# MB1-Pwr-r1_0.net
KiCad netlist of a schematic drawn in Altium Designer
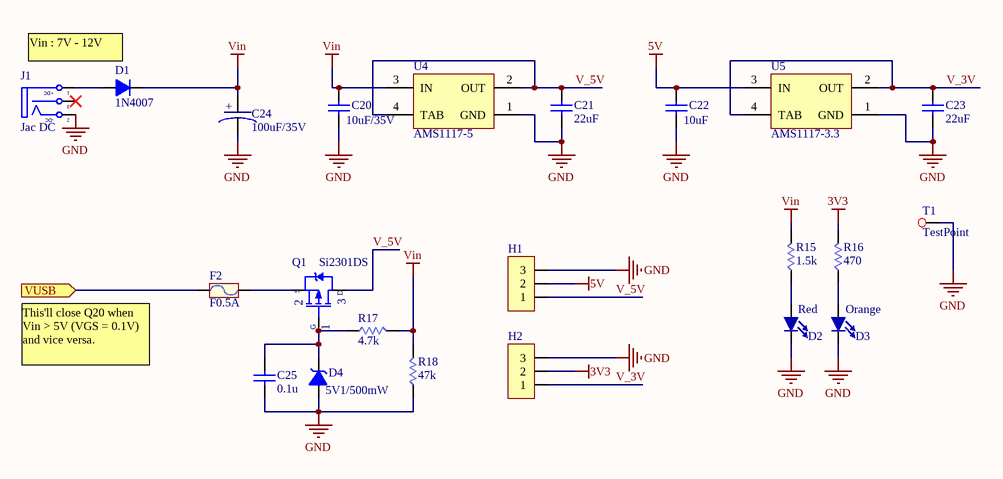
[diagram p0: MB1-Pwr-r1.0.SchDoc]

(export (version "E")
  (design (tool "Eeschema 10.0.6"))
  (components
    (comp (ref "C20")
      (value "10uF/35V")
      (footprint "SM-1210")
      (description "Non-polarity ceramic capacitor")
      (fields (field (name "Comment") "CAP Ceramic") (field (name "PUBLISHER") "Altium Limited"))
      (libsource (lib "HLib_schematic_lib") (part "CAP Ceramic"))
    )
    (comp (ref "C21")
      (value "22uF")
      (footprint "SM_0805_C_CERAMIC")
      (description "Non-polarity ceramic capacitor")
      (fields (field (name "Comment") "CAP Ceramic") (field (name "PUBLISHER") "Altium Limited"))
      (libsource (lib "HLib_schematic_lib") (part "CAP Ceramic"))
    )
    (comp (ref "C22")
      (value "10uF")
      (footprint "SM_0805_C_CERAMIC")
      (description "Non-polarity ceramic capacitor")
      (fields (field (name "Comment") "CAP Ceramic") (field (name "PUBLISHER") "Altium Limited"))
      (libsource (lib "HLib_schematic_lib") (part "CAP Ceramic"))
    )
    (comp (ref "C23")
      (value "22uF")
      (footprint "SM_0805_C_CERAMIC")
      (description "Non-polarity ceramic capacitor")
      (fields (field (name "Comment") "CAP Ceramic") (field (name "PUBLISHER") "Altium Limited"))
      (libsource (lib "HLib_schematic_lib") (part "CAP Ceramic"))
    )
    (comp (ref "C24")
      (value "100uF/35V")
      (footprint "Cap-Alu-D8")
      (fields (field (name "Comment") "CapT"))
      (libsource (lib "MyLib") (part "CapA"))
    )
    (comp (ref "C25")
      (value "0.1u")
      (footprint "SM_0805_C_CERAMIC")
      (description "Non-polarity ceramic capacitor")
      (fields (field (name "Comment") "CAP Ceramic") (field (name "PUBLISHER") "Altium Limited"))
      (libsource (lib "HLib_schematic_lib") (part "CAP Ceramic"))
    )
    (comp (ref "D1")
      (value "1N4007")
      (footprint "DO-214AC")
      (description "Diode 1A")
      (libsource (lib "VioletofSun") (part "D1A"))
    )
    (comp (ref "D2")
      (value "Red")
      (footprint "SM_0805_POL_LD")
      (description "LED")
      (fields (field (name "PUBLISHER") "Altium Limited"))
      (libsource (lib "HLib_schematic_lib") (part "LED"))
    )
    (comp (ref "D3")
      (value "Orange")
      (footprint "SM_0805_POL_LD")
      (description "LED")
      (fields (field (name "PUBLISHER") "Altium Limited"))
      (libsource (lib "HLib_schematic_lib") (part "LED"))
    )
    (comp (ref "D4")
      (value "5V1/500mW")
      (footprint "SOD-123")
      (description "Diode Zenner")
      (libsource (lib "VioletofSun") (part "DZ"))
    )
    (comp (ref "F2")
      (value "F0.5A")
      (footprint "SMD-1812")
      (description "Fuse")
      (fields (field (name "DESIGNED BY") "VanDungEvn"))
      (libsource (lib "VioletofSun") (part "Fuse"))
    )
    (comp (ref "H1") (value "Hed3") (footprint "Hed3") (libsource (lib "MyLib") (part "Hed3")))
    (comp (ref "H2") (value "Hed3") (footprint "Hed3") (libsource (lib "MyLib") (part "Hed3")))
    (comp (ref "J1")
      (value "Jac DC")
      (footprint "DCJack")
      (description "Jac DC input")
      (libsource (lib "VioletofSun") (part "DCIN"))
    )
    (comp (ref "Q1")
      (value "Si2301DS")
      (footprint "SOT23")
      (description "P-Channel 1.25-W, 2.5-V MOSFET")
      (libsource (lib "MyLib") (part "P-MOSFET"))
    )
    (comp (ref "R15")
      (value "1.5k")
      (footprint "SM_0805_R")
      (description "Resistor")
      (fields (field (name "PUBLISHER") "Altium Limited"))
      (libsource (lib "HLib_schematic_lib") (part "R"))
    )
    (comp (ref "R16")
      (value "470")
      (footprint "SM_0805_R")
      (description "Resistor")
      (fields (field (name "PUBLISHER") "Altium Limited"))
      (libsource (lib "HLib_schematic_lib") (part "R"))
    )
    (comp (ref "R17")
      (value "4.7k")
      (footprint "SM_0805_R")
      (description "Resistor")
      (fields (field (name "PUBLISHER") "Altium Limited"))
      (libsource (lib "HLib_schematic_lib") (part "R"))
    )
    (comp (ref "R18")
      (value "47k")
      (footprint "SM_0805_R")
      (description "Resistor")
      (fields (field (name "PUBLISHER") "Altium Limited"))
      (libsource (lib "HLib_schematic_lib") (part "R"))
    )
    (comp (ref "T1") (value "TestPoint") (footprint "TestPoint") (libsource (lib "MyLib") (part "TestPoint")))
    (comp (ref "U4")
      (value "AMS1117-5")
      (footprint "MP04A_N")
      (description "800mA Low-Dropout Linear Regulator, 4-pin SOT-223")
      (fields
        (field (name "PARTNUMBER") "LM1117IMP-3.3")
        (field (name "MANUFACTURER") "National Semiconductor")
        (field (name "PUBLISHER") "Altium Limited")
      )
      (libsource (lib "NSC LDO") (part "LM1117IMP-3.3"))
    )
    (comp (ref "U5")
      (value "AMS1117-3.3")
      (footprint "MP04A_N")
      (description "800mA Low-Dropout Linear Regulator, 4-pin SOT-223")
      (fields
        (field (name "PARTNUMBER") "LM1117IMP-3.3")
        (field (name "MANUFACTURER") "National Semiconductor")
        (field (name "PUBLISHER") "Altium Limited")
      )
      (libsource (lib "NSC LDO") (part "LM1117IMP-3.3"))
    )
  )
  (nets
    (net (code "1") (name "/VUSB") (class "Default")
      (node (ref "F2") (pin "1") (pinfunction "1_1") (pintype "passive"))
    )
    (net (code "2") (name "/V_3V") (class "Default")
      (node (ref "C23") (pin "2") (pinfunction "2_2") (pintype "passive"))
      (node (ref "H2") (pin "1") (pinfunction "1_1") (pintype "passive"))
      (node (ref "U5") (pin "2") (pinfunction "OUT_2") (pintype "power_in"))
      (node (ref "U5") (pin "4") (pinfunction "TAB_4") (pintype "power_in"))
    )
    (net (code "3") (name "/V_5V") (class "Default")
      (node (ref "C21") (pin "2") (pinfunction "2_2") (pintype "passive"))
      (node (ref "H1") (pin "1") (pinfunction "1_1") (pintype "passive"))
      (node (ref "Q1") (pin "3") (pinfunction "D_3") (pintype "passive"))
      (node (ref "U4") (pin "2") (pinfunction "OUT_2") (pintype "power_in"))
      (node (ref "U4") (pin "4") (pinfunction "TAB_4") (pintype "power_in"))
    )
    (net (code "4") (name "3V3") (class "Default")
      (node (ref "H2") (pin "2") (pinfunction "2_2") (pintype "passive"))
      (node (ref "R16") (pin "2") (pinfunction "2_2") (pintype "passive"))
    )
    (net (code "5") (name "5V") (class "Default")
      (node (ref "C22") (pin "2") (pinfunction "2_2") (pintype "passive"))
      (node (ref "H1") (pin "2") (pinfunction "2_2") (pintype "passive"))
      (node (ref "U5") (pin "3") (pinfunction "IN_3") (pintype "power_in"))
    )
    (net (code "6") (name "GND") (class "Default")
      (node (ref "C20") (pin "1") (pinfunction "1_1") (pintype "passive"))
      (node (ref "C21") (pin "1") (pinfunction "1_1") (pintype "passive"))
      (node (ref "C22") (pin "1") (pinfunction "1_1") (pintype "passive"))
      (node (ref "C23") (pin "1") (pinfunction "1_1") (pintype "passive"))
      (node (ref "C24") (pin "2") (pinfunction "-_2") (pintype "passive"))
      (node (ref "C25") (pin "1") (pinfunction "1_1") (pintype "passive"))
      (node (ref "D2") (pin "2") (pinfunction "K_2") (pintype "passive"))
      (node (ref "D3") (pin "2") (pinfunction "K_2") (pintype "passive"))
      (node (ref "D4") (pin "1") (pinfunction "A_1") (pintype "passive"))
      (node (ref "H1") (pin "3") (pinfunction "3_3") (pintype "passive"))
      (node (ref "H2") (pin "3") (pinfunction "3_3") (pintype "passive"))
      (node (ref "J1") (pin "2") (pinfunction "TN_2") (pintype "passive"))
      (node (ref "R18") (pin "1") (pinfunction "1_1") (pintype "passive"))
      (node (ref "T1") (pin "1") (pinfunction "0_1") (pintype "passive"))
      (node (ref "U4") (pin "1") (pinfunction "GND_1") (pintype "power_in"))
      (node (ref "U5") (pin "1") (pinfunction "GND_1") (pintype "power_in"))
    )
    (net (code "7") (name "Net-(D1-A)") (class "Default")
      (node (ref "D1") (pin "1") (pinfunction "A_1") (pintype "passive"))
      (node (ref "J1") (pin "1") (pinfunction "T_1") (pintype "passive"))
    )
    (net (code "8") (name "Net-(D2-A)") (class "Default")
      (node (ref "D2") (pin "1") (pinfunction "A_1") (pintype "passive"))
      (node (ref "R15") (pin "1") (pinfunction "1_1") (pintype "passive"))
    )
    (net (code "9") (name "Net-(D3-A)") (class "Default")
      (node (ref "D3") (pin "1") (pinfunction "A_1") (pintype "passive"))
      (node (ref "R16") (pin "1") (pinfunction "1_1") (pintype "passive"))
    )
    (net (code "10") (name "Net-(D4-K)") (class "Default")
      (node (ref "C25") (pin "2") (pinfunction "2_2") (pintype "passive"))
      (node (ref "D4") (pin "2") (pinfunction "K_2") (pintype "passive"))
      (node (ref "Q1") (pin "1") (pinfunction "G_1") (pintype "passive"))
      (node (ref "R17") (pin "1") (pinfunction "1_1") (pintype "passive"))
    )
    (net (code "11") (name "Net-(Q1-S)") (class "Default")
      (node (ref "F2") (pin "2") (pinfunction "2_2") (pintype "passive"))
      (node (ref "Q1") (pin "2") (pinfunction "S_2") (pintype "passive"))
    )
    (net (code "12") (name "Vin") (class "Default")
      (node (ref "C20") (pin "2") (pinfunction "2_2") (pintype "passive"))
      (node (ref "C24") (pin "1") (pinfunction "+_1") (pintype "passive"))
      (node (ref "D1") (pin "2") (pinfunction "K_2") (pintype "passive"))
      (node (ref "R15") (pin "2") (pinfunction "2_2") (pintype "passive"))
      (node (ref "R17") (pin "2") (pinfunction "2_2") (pintype "passive"))
      (node (ref "R18") (pin "2") (pinfunction "2_2") (pintype "passive"))
      (node (ref "U4") (pin "3") (pinfunction "IN_3") (pintype "power_in"))
    )
    (net (code "13") (name "unconnected-(J1-S-Pad3)") (class "Default")
      (node (ref "J1") (pin "3") (pinfunction "S_3") (pintype "power_in+no_connect"))
    )
  )
)
